# JurgenFolder.net
KiCad netlist of a schematic drawn in EAGLE
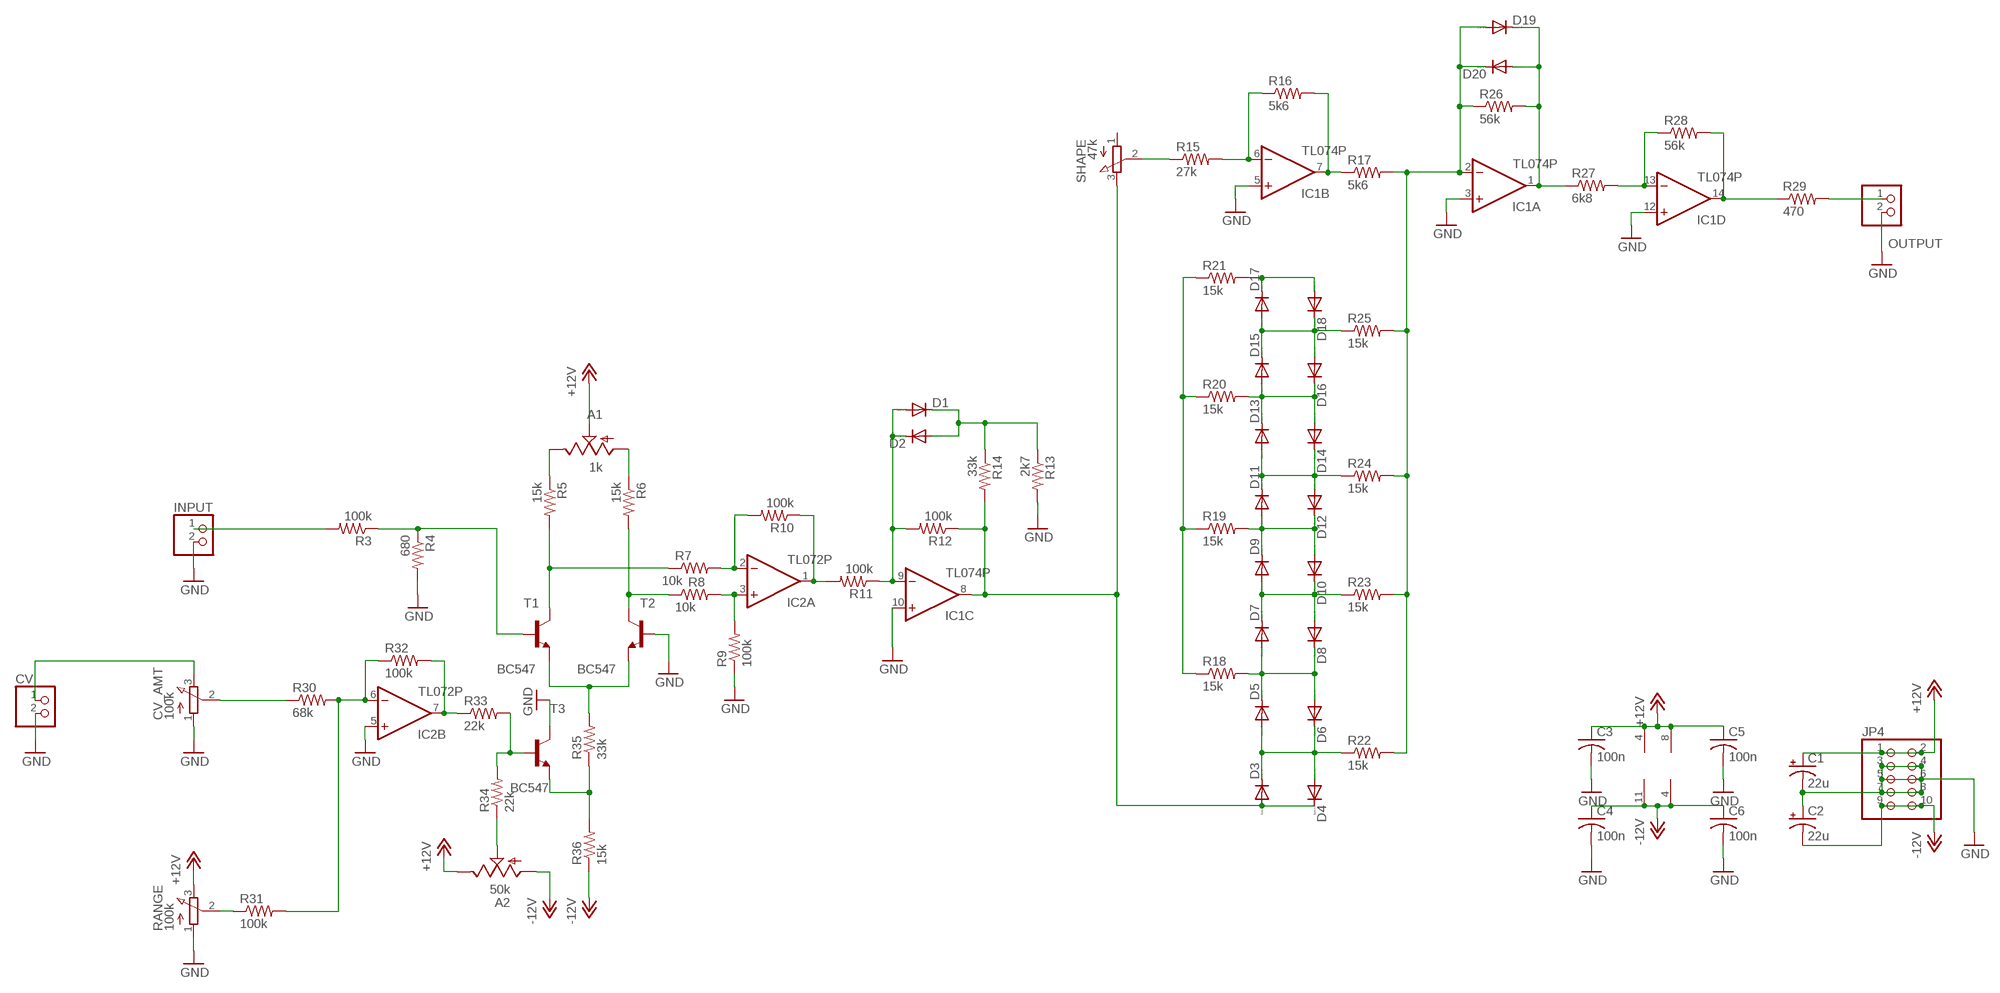
[diagram p0: schematic, sheet 1]

(export (version "E")
  (design (tool "Eeschema 10.0.6"))
  (components
    (comp (ref "A1")
      (value "1k")
      (footprint "eagle-import:S64W")
      (libsource (lib "eagle-import") (part "TRIM_US-S64W"))
    )
    (comp (ref "A2")
      (value "50k")
      (footprint "eagle-import:S64W")
      (libsource (lib "eagle-import") (part "TRIM_US-S64W"))
    )
    (comp (ref "C1")
      (value "22u")
      (footprint "eagle-import:E3,5-8")
      (libsource (lib "eagle-import") (part "CPOL-USE3.5-8"))
    )
    (comp (ref "C2")
      (value "22u")
      (footprint "eagle-import:E3,5-8")
      (libsource (lib "eagle-import") (part "CPOL-USE3.5-8"))
    )
    (comp (ref "C3")
      (value "100n")
      (footprint "eagle-import:C025-030X050")
      (libsource (lib "eagle-import") (part "C-US025-030X050"))
    )
    (comp (ref "C4")
      (value "100n")
      (footprint "eagle-import:C025-030X050")
      (libsource (lib "eagle-import") (part "C-US025-030X050"))
    )
    (comp (ref "C5")
      (value "100n")
      (footprint "eagle-import:C025-030X050")
      (libsource (lib "eagle-import") (part "C-US025-030X050"))
    )
    (comp (ref "C6")
      (value "100n")
      (footprint "eagle-import:C025-030X050")
      (libsource (lib "eagle-import") (part "C-US025-030X050"))
    )
    (comp (ref "CV")
      (value "PINHD-1X2")
      (footprint "eagle-import:1X02")
      (libsource (lib "eagle-import") (part "PINHD-1X2"))
    )
    (comp (ref "CV_AMT")
      (value "100k")
      (footprint "eagle-import:3RP_1610N")
      (libsource (lib "eagle-import") (part "3RP/1610N"))
    )
    (comp (ref "D1")
      (value "1N4148DO35-7")
      (footprint "eagle-import:DO35-7")
      (libsource (lib "eagle-import") (part "1N4148DO35-7"))
    )
    (comp (ref "D2")
      (value "1N4148DO35-7")
      (footprint "eagle-import:DO35-7")
      (libsource (lib "eagle-import") (part "1N4148DO35-7"))
    )
    (comp (ref "D3")
      (value "1N4148DO35-7")
      (footprint "eagle-import:DO35-7")
      (libsource (lib "eagle-import") (part "1N4148DO35-7"))
    )
    (comp (ref "D4")
      (value "1N4148DO35-7")
      (footprint "eagle-import:DO35-7")
      (libsource (lib "eagle-import") (part "1N4148DO35-7"))
    )
    (comp (ref "D5")
      (value "1N4148DO35-7")
      (footprint "eagle-import:DO35-7")
      (libsource (lib "eagle-import") (part "1N4148DO35-7"))
    )
    (comp (ref "D6")
      (value "1N4148DO35-7")
      (footprint "eagle-import:DO35-7")
      (libsource (lib "eagle-import") (part "1N4148DO35-7"))
    )
    (comp (ref "D7")
      (value "1N4148DO35-7")
      (footprint "eagle-import:DO35-7")
      (libsource (lib "eagle-import") (part "1N4148DO35-7"))
    )
    (comp (ref "D8")
      (value "1N4148DO35-7")
      (footprint "eagle-import:DO35-7")
      (libsource (lib "eagle-import") (part "1N4148DO35-7"))
    )
    (comp (ref "D9")
      (value "1N4148DO35-7")
      (footprint "eagle-import:DO35-7")
      (libsource (lib "eagle-import") (part "1N4148DO35-7"))
    )
    (comp (ref "D10")
      (value "1N4148DO35-7")
      (footprint "eagle-import:DO35-7")
      (libsource (lib "eagle-import") (part "1N4148DO35-7"))
    )
    (comp (ref "D11")
      (value "1N4148DO35-7")
      (footprint "eagle-import:DO35-7")
      (libsource (lib "eagle-import") (part "1N4148DO35-7"))
    )
    (comp (ref "D12")
      (value "1N4148DO35-7")
      (footprint "eagle-import:DO35-7")
      (libsource (lib "eagle-import") (part "1N4148DO35-7"))
    )
    (comp (ref "D13")
      (value "1N4148DO35-7")
      (footprint "eagle-import:DO35-7")
      (libsource (lib "eagle-import") (part "1N4148DO35-7"))
    )
    (comp (ref "D14")
      (value "1N4148DO35-7")
      (footprint "eagle-import:DO35-7")
      (libsource (lib "eagle-import") (part "1N4148DO35-7"))
    )
    (comp (ref "D15")
      (value "1N4148DO35-7")
      (footprint "eagle-import:DO35-7")
      (libsource (lib "eagle-import") (part "1N4148DO35-7"))
    )
    (comp (ref "D16")
      (value "1N4148DO35-7")
      (footprint "eagle-import:DO35-7")
      (libsource (lib "eagle-import") (part "1N4148DO35-7"))
    )
    (comp (ref "D17")
      (value "1N4148DO35-7")
      (footprint "eagle-import:DO35-7")
      (libsource (lib "eagle-import") (part "1N4148DO35-7"))
    )
    (comp (ref "D18")
      (value "1N4148DO35-7")
      (footprint "eagle-import:DO35-7")
      (libsource (lib "eagle-import") (part "1N4148DO35-7"))
    )
    (comp (ref "D19")
      (value "1N4148DO35-7")
      (footprint "eagle-import:DO35-7")
      (libsource (lib "eagle-import") (part "1N4148DO35-7"))
    )
    (comp (ref "D20")
      (value "1N4148DO35-7")
      (footprint "eagle-import:DO35-7")
      (libsource (lib "eagle-import") (part "1N4148DO35-7"))
    )
    (comp (ref "IC1")
      (value "TL074P")
      (footprint "eagle-import:DIL14")
      (libsource (lib "eagle-import") (part "TL074P"))
    )
    (comp (ref "IC2")
      (value "TL072P")
      (footprint "eagle-import:DIL08")
      (libsource (lib "eagle-import") (part "TL072P"))
    )
    (comp (ref "INPUT")
      (value "PINHD-1X2")
      (footprint "eagle-import:1X02")
      (libsource (lib "eagle-import") (part "PINHD-1X2"))
    )
    (comp (ref "JP4")
      (value "PINHD-2X5")
      (footprint "eagle-import:2X05")
      (libsource (lib "eagle-import") (part "PINHD-2X5"))
    )
    (comp (ref "OUTPUT")
      (value "PINHD-1X2")
      (footprint "eagle-import:1X02")
      (libsource (lib "eagle-import") (part "PINHD-1X2"))
    )
    (comp (ref "R3")
      (value "100k")
      (footprint "eagle-import:0204_7")
      (libsource (lib "eagle-import") (part "R-US_0204/7"))
    )
    (comp (ref "R4")
      (value "680")
      (footprint "eagle-import:0204_7")
      (libsource (lib "eagle-import") (part "R-US_0204/7"))
    )
    (comp (ref "R5")
      (value "15k")
      (footprint "eagle-import:0204_7")
      (libsource (lib "eagle-import") (part "R-US_0204/7"))
    )
    (comp (ref "R6")
      (value "15k")
      (footprint "eagle-import:0204_7")
      (libsource (lib "eagle-import") (part "R-US_0204/7"))
    )
    (comp (ref "R7")
      (value "10k")
      (footprint "eagle-import:0204_7")
      (libsource (lib "eagle-import") (part "R-US_0204/7"))
    )
    (comp (ref "R8")
      (value "10k")
      (footprint "eagle-import:0204_7")
      (libsource (lib "eagle-import") (part "R-US_0204/7"))
    )
    (comp (ref "R9")
      (value "100k")
      (footprint "eagle-import:0204_7")
      (libsource (lib "eagle-import") (part "R-US_0204/7"))
    )
    (comp (ref "R10")
      (value "100k")
      (footprint "eagle-import:0204_7")
      (libsource (lib "eagle-import") (part "R-US_0204/7"))
    )
    (comp (ref "R11")
      (value "100k")
      (footprint "eagle-import:0204_7")
      (libsource (lib "eagle-import") (part "R-US_0204/7"))
    )
    (comp (ref "R12")
      (value "100k")
      (footprint "eagle-import:0204_7")
      (libsource (lib "eagle-import") (part "R-US_0204/7"))
    )
    (comp (ref "R13")
      (value "2k7")
      (footprint "eagle-import:0204_7")
      (libsource (lib "eagle-import") (part "R-US_0204/7"))
    )
    (comp (ref "R14")
      (value "33k")
      (footprint "eagle-import:0204_7")
      (libsource (lib "eagle-import") (part "R-US_0204/7"))
    )
    (comp (ref "R15")
      (value "27k")
      (footprint "eagle-import:0204_7")
      (libsource (lib "eagle-import") (part "R-US_0204/7"))
    )
    (comp (ref "R16")
      (value "5k6")
      (footprint "eagle-import:0204_7")
      (libsource (lib "eagle-import") (part "R-US_0204/7"))
    )
    (comp (ref "R17")
      (value "5k6")
      (footprint "eagle-import:0204_7")
      (libsource (lib "eagle-import") (part "R-US_0204/7"))
    )
    (comp (ref "R18")
      (value "15k")
      (footprint "eagle-import:0204_7")
      (libsource (lib "eagle-import") (part "R-US_0204/7"))
    )
    (comp (ref "R19")
      (value "15k")
      (footprint "eagle-import:0204_7")
      (libsource (lib "eagle-import") (part "R-US_0204/7"))
    )
    (comp (ref "R20")
      (value "15k")
      (footprint "eagle-import:0204_7")
      (libsource (lib "eagle-import") (part "R-US_0204/7"))
    )
    (comp (ref "R21")
      (value "15k")
      (footprint "eagle-import:0204_7")
      (libsource (lib "eagle-import") (part "R-US_0204/7"))
    )
    (comp (ref "R22")
      (value "15k")
      (footprint "eagle-import:0204_7")
      (libsource (lib "eagle-import") (part "R-US_0204/7"))
    )
    (comp (ref "R23")
      (value "15k")
      (footprint "eagle-import:0204_7")
      (libsource (lib "eagle-import") (part "R-US_0204/7"))
    )
    (comp (ref "R24")
      (value "15k")
      (footprint "eagle-import:0204_7")
      (libsource (lib "eagle-import") (part "R-US_0204/7"))
    )
    (comp (ref "R25")
      (value "15k")
      (footprint "eagle-import:0204_7")
      (libsource (lib "eagle-import") (part "R-US_0204/7"))
    )
    (comp (ref "R26")
      (value "56k")
      (footprint "eagle-import:0204_7")
      (libsource (lib "eagle-import") (part "R-US_0204/7"))
    )
    (comp (ref "R27")
      (value "6k8")
      (footprint "eagle-import:0204_7")
      (libsource (lib "eagle-import") (part "R-US_0204/7"))
    )
    (comp (ref "R28")
      (value "56k")
      (footprint "eagle-import:0204_7")
      (libsource (lib "eagle-import") (part "R-US_0204/7"))
    )
    (comp (ref "R29")
      (value "470")
      (footprint "eagle-import:0204_7")
      (libsource (lib "eagle-import") (part "R-US_0204/7"))
    )
    (comp (ref "R30")
      (value "68k")
      (footprint "eagle-import:0204_7")
      (libsource (lib "eagle-import") (part "R-US_0204/7"))
    )
    (comp (ref "R31")
      (value "100k")
      (footprint "eagle-import:0204_7")
      (libsource (lib "eagle-import") (part "R-US_0204/7"))
    )
    (comp (ref "R32")
      (value "100k")
      (footprint "eagle-import:0204_7")
      (libsource (lib "eagle-import") (part "R-US_0204/7"))
    )
    (comp (ref "R33")
      (value "22k")
      (footprint "eagle-import:0204_7")
      (libsource (lib "eagle-import") (part "R-US_0204/7"))
    )
    (comp (ref "R34")
      (value "22k")
      (footprint "eagle-import:0204_7")
      (libsource (lib "eagle-import") (part "R-US_0204/7"))
    )
    (comp (ref "R35")
      (value "33k")
      (footprint "eagle-import:0204_7")
      (libsource (lib "eagle-import") (part "R-US_0204/7"))
    )
    (comp (ref "R36")
      (value "15k")
      (footprint "eagle-import:0204_7")
      (libsource (lib "eagle-import") (part "R-US_0204/7"))
    )
    (comp (ref "RANGE")
      (value "100k")
      (footprint "eagle-import:3RP_1610N")
      (libsource (lib "eagle-import") (part "3RP/1610N"))
    )
    (comp (ref "SHAPE")
      (value "47k")
      (footprint "eagle-import:3RP_1610N")
      (libsource (lib "eagle-import") (part "3RP/1610N"))
    )
    (comp (ref "T1")
      (value "BC547")
      (footprint "eagle-import:TO92")
      (libsource (lib "eagle-import") (part "BC547"))
    )
    (comp (ref "T2")
      (value "BC547")
      (footprint "eagle-import:TO92")
      (libsource (lib "eagle-import") (part "BC547"))
    )
    (comp (ref "T3")
      (value "BC547")
      (footprint "eagle-import:TO92")
      (libsource (lib "eagle-import") (part "BC547"))
    )
  )
  (nets
    (net (code "1") (name "+12V") (class "Default")
      (node (ref "A1") (pin "S") (pinfunction "S_S") (pintype "passive"))
      (node (ref "A2") (pin "E") (pinfunction "E_E") (pintype "passive"))
      (node (ref "C1") (pin "+") (pinfunction "+_+") (pintype "passive"))
      (node (ref "C3") (pin "1") (pinfunction "1_1") (pintype "passive"))
      (node (ref "C5") (pin "1") (pinfunction "1_1") (pintype "passive"))
      (node (ref "IC1") (pin "4") (pinfunction "V+_4") (pintype "power_in"))
      (node (ref "IC2") (pin "8") (pinfunction "V+_8") (pintype "power_in"))
      (node (ref "JP4") (pin "1") (pinfunction "1_1") (pintype "passive"))
      (node (ref "JP4") (pin "2") (pinfunction "2_2") (pintype "passive"))
      (node (ref "RANGE") (pin "3") (pinfunction "E_3") (pintype "passive"))
    )
    (net (code "2") (name "-12V") (class "Default")
      (node (ref "A2") (pin "A") (pinfunction "A_A") (pintype "passive"))
      (node (ref "C2") (pin "-") (pinfunction "-_-") (pintype "passive"))
      (node (ref "C4") (pin "1") (pinfunction "1_1") (pintype "passive"))
      (node (ref "C6") (pin "1") (pinfunction "1_1") (pintype "passive"))
      (node (ref "IC1") (pin "11") (pinfunction "V-_11") (pintype "power_in"))
      (node (ref "IC2") (pin "4") (pinfunction "V-_4") (pintype "power_in"))
      (node (ref "JP4") (pin "10") (pinfunction "10_10") (pintype "passive"))
      (node (ref "JP4") (pin "9") (pinfunction "9_9") (pintype "passive"))
      (node (ref "R36") (pin "1") (pinfunction "1_1") (pintype "passive"))
    )
    (net (code "3") (name "GND") (class "Default")
      (node (ref "C1") (pin "-") (pinfunction "-_-") (pintype "passive"))
      (node (ref "C2") (pin "+") (pinfunction "+_+") (pintype "passive"))
      (node (ref "C3") (pin "2") (pinfunction "2_2") (pintype "passive"))
      (node (ref "C4") (pin "2") (pinfunction "2_2") (pintype "passive"))
      (node (ref "C5") (pin "2") (pinfunction "2_2") (pintype "passive"))
      (node (ref "C6") (pin "2") (pinfunction "2_2") (pintype "passive"))
      (node (ref "CV") (pin "2") (pinfunction "2_2") (pintype "passive"))
      (node (ref "CV_AMT") (pin "1") (pinfunction "A_1") (pintype "passive"))
      (node (ref "IC1") (pin "10") (pinfunction "+IN_10") (pintype "input"))
      (node (ref "IC1") (pin "12") (pinfunction "+IN_12") (pintype "input"))
      (node (ref "IC1") (pin "3") (pinfunction "+IN_3") (pintype "input"))
      (node (ref "IC1") (pin "5") (pinfunction "+IN_5") (pintype "input"))
      (node (ref "IC2") (pin "5") (pinfunction "+IN_5") (pintype "input"))
      (node (ref "INPUT") (pin "2") (pinfunction "2_2") (pintype "passive"))
      (node (ref "JP4") (pin "3") (pinfunction "3_3") (pintype "passive"))
      (node (ref "JP4") (pin "4") (pinfunction "4_4") (pintype "passive"))
      (node (ref "JP4") (pin "5") (pinfunction "5_5") (pintype "passive"))
      (node (ref "JP4") (pin "6") (pinfunction "6_6") (pintype "passive"))
      (node (ref "JP4") (pin "7") (pinfunction "7_7") (pintype "passive"))
      (node (ref "JP4") (pin "8") (pinfunction "8_8") (pintype "passive"))
      (node (ref "OUTPUT") (pin "2") (pinfunction "2_2") (pintype "passive"))
      (node (ref "R13") (pin "2") (pinfunction "2_2") (pintype "passive"))
      (node (ref "R4") (pin "2") (pinfunction "2_2") (pintype "passive"))
      (node (ref "R9") (pin "1") (pinfunction "1_1") (pintype "passive"))
      (node (ref "RANGE") (pin "1") (pinfunction "A_1") (pintype "passive"))
      (node (ref "T2") (pin "2") (pinfunction "B_2") (pintype "passive"))
      (node (ref "T3") (pin "3") (pinfunction "C_3") (pintype "passive"))
    )
    (net (code "4") (name "Net-(A1-PadA)") (class "Default")
      (node (ref "A1") (pin "A") (pinfunction "A_A") (pintype "passive"))
      (node (ref "R6") (pin "1") (pinfunction "1_1") (pintype "passive"))
    )
    (net (code "5") (name "Net-(A1-PadE)") (class "Default")
      (node (ref "A1") (pin "E") (pinfunction "E_E") (pintype "passive"))
      (node (ref "R5") (pin "1") (pinfunction "1_1") (pintype "passive"))
    )
    (net (code "6") (name "Net-(A2-PadS)") (class "Default")
      (node (ref "A2") (pin "S") (pinfunction "S_S") (pintype "passive"))
      (node (ref "R34") (pin "1") (pinfunction "1_1") (pintype "passive"))
    )
    (net (code "7") (name "Net-(CV_AMT-E)") (class "Default")
      (node (ref "CV") (pin "1") (pinfunction "1_1") (pintype "passive"))
      (node (ref "CV_AMT") (pin "3") (pinfunction "E_3") (pintype "passive"))
    )
    (net (code "8") (name "Net-(CV_AMT-S)") (class "Default")
      (node (ref "CV_AMT") (pin "2") (pinfunction "S_2") (pintype "passive"))
      (node (ref "R30") (pin "1") (pinfunction "1_1") (pintype "passive"))
    )
    (net (code "9") (name "Net-(D1-PadC)") (class "Default")
      (node (ref "D1") (pin "C") (pinfunction "C_C") (pintype "passive"))
      (node (ref "D2") (pin "A") (pinfunction "A_A") (pintype "passive"))
      (node (ref "R13") (pin "1") (pinfunction "1_1") (pintype "passive"))
      (node (ref "R14") (pin "1") (pinfunction "1_1") (pintype "passive"))
    )
    (net (code "10") (name "Net-(D3-PadC)") (class "Default")
      (node (ref "D3") (pin "C") (pinfunction "C_C") (pintype "passive"))
      (node (ref "D4") (pin "A") (pinfunction "A_A") (pintype "passive"))
      (node (ref "D5") (pin "A") (pinfunction "A_A") (pintype "passive"))
      (node (ref "D6") (pin "C") (pinfunction "C_C") (pintype "passive"))
      (node (ref "R22") (pin "1") (pinfunction "1_1") (pintype "passive"))
    )
    (net (code "11") (name "Net-(D5-PadC)") (class "Default")
      (node (ref "D5") (pin "C") (pinfunction "C_C") (pintype "passive"))
      (node (ref "D6") (pin "A") (pinfunction "A_A") (pintype "passive"))
      (node (ref "D7") (pin "A") (pinfunction "A_A") (pintype "passive"))
      (node (ref "D8") (pin "C") (pinfunction "C_C") (pintype "passive"))
      (node (ref "R18") (pin "2") (pinfunction "2_2") (pintype "passive"))
    )
    (net (code "12") (name "Net-(D10-PadA)") (class "Default")
      (node (ref "D10") (pin "A") (pinfunction "A_A") (pintype "passive"))
      (node (ref "D11") (pin "A") (pinfunction "A_A") (pintype "passive"))
      (node (ref "D12") (pin "C") (pinfunction "C_C") (pintype "passive"))
      (node (ref "D9") (pin "C") (pinfunction "C_C") (pintype "passive"))
      (node (ref "R19") (pin "2") (pinfunction "2_2") (pintype "passive"))
    )
    (net (code "13") (name "Net-(D10-PadC)") (class "Default")
      (node (ref "D10") (pin "C") (pinfunction "C_C") (pintype "passive"))
      (node (ref "D7") (pin "C") (pinfunction "C_C") (pintype "passive"))
      (node (ref "D8") (pin "A") (pinfunction "A_A") (pintype "passive"))
      (node (ref "D9") (pin "A") (pinfunction "A_A") (pintype "passive"))
      (node (ref "R23") (pin "1") (pinfunction "1_1") (pintype "passive"))
    )
    (net (code "14") (name "Net-(D11-PadC)") (class "Default")
      (node (ref "D11") (pin "C") (pinfunction "C_C") (pintype "passive"))
      (node (ref "D12") (pin "A") (pinfunction "A_A") (pintype "passive"))
      (node (ref "D13") (pin "A") (pinfunction "A_A") (pintype "passive"))
      (node (ref "D14") (pin "C") (pinfunction "C_C") (pintype "passive"))
      (node (ref "R24") (pin "1") (pinfunction "1_1") (pintype "passive"))
    )
    (net (code "15") (name "Net-(D13-PadC)") (class "Default")
      (node (ref "D13") (pin "C") (pinfunction "C_C") (pintype "passive"))
      (node (ref "D14") (pin "A") (pinfunction "A_A") (pintype "passive"))
      (node (ref "D15") (pin "A") (pinfunction "A_A") (pintype "passive"))
      (node (ref "D16") (pin "C") (pinfunction "C_C") (pintype "passive"))
      (node (ref "R20") (pin "2") (pinfunction "2_2") (pintype "passive"))
    )
    (net (code "16") (name "Net-(D15-PadC)") (class "Default")
      (node (ref "D15") (pin "C") (pinfunction "C_C") (pintype "passive"))
      (node (ref "D16") (pin "A") (pinfunction "A_A") (pintype "passive"))
      (node (ref "D17") (pin "A") (pinfunction "A_A") (pintype "passive"))
      (node (ref "D18") (pin "C") (pinfunction "C_C") (pintype "passive"))
      (node (ref "R25") (pin "1") (pinfunction "1_1") (pintype "passive"))
    )
    (net (code "17") (name "Net-(D17-PadC)") (class "Default")
      (node (ref "D17") (pin "C") (pinfunction "C_C") (pintype "passive"))
      (node (ref "D18") (pin "A") (pinfunction "A_A") (pintype "passive"))
      (node (ref "R21") (pin "2") (pinfunction "2_2") (pintype "passive"))
    )
    (net (code "18") (name "Net-(IC1A--IN)") (class "Default")
      (node (ref "D19") (pin "A") (pinfunction "A_A") (pintype "passive"))
      (node (ref "D20") (pin "C") (pinfunction "C_C") (pintype "passive"))
      (node (ref "IC1") (pin "2") (pinfunction "-IN_2") (pintype "input"))
      (node (ref "R17") (pin "2") (pinfunction "2_2") (pintype "passive"))
      (node (ref "R22") (pin "2") (pinfunction "2_2") (pintype "passive"))
      (node (ref "R23") (pin "2") (pinfunction "2_2") (pintype "passive"))
      (node (ref "R24") (pin "2") (pinfunction "2_2") (pintype "passive"))
      (node (ref "R25") (pin "2") (pinfunction "2_2") (pintype "passive"))
      (node (ref "R26") (pin "1") (pinfunction "1_1") (pintype "passive"))
    )
    (net (code "19") (name "Net-(IC1A-OUT)") (class "Default")
      (node (ref "D19") (pin "C") (pinfunction "C_C") (pintype "passive"))
      (node (ref "D20") (pin "A") (pinfunction "A_A") (pintype "passive"))
      (node (ref "IC1") (pin "1") (pinfunction "OUT_1") (pintype "output"))
      (node (ref "R26") (pin "2") (pinfunction "2_2") (pintype "passive"))
      (node (ref "R27") (pin "1") (pinfunction "1_1") (pintype "passive"))
    )
    (net (code "20") (name "Net-(IC1B--IN)") (class "Default")
      (node (ref "IC1") (pin "6") (pinfunction "-IN_6") (pintype "input"))
      (node (ref "R15") (pin "2") (pinfunction "2_2") (pintype "passive"))
      (node (ref "R16") (pin "1") (pinfunction "1_1") (pintype "passive"))
    )
    (net (code "21") (name "Net-(IC1B-OUT)") (class "Default")
      (node (ref "IC1") (pin "7") (pinfunction "OUT_7") (pintype "output"))
      (node (ref "R16") (pin "2") (pinfunction "2_2") (pintype "passive"))
      (node (ref "R17") (pin "1") (pinfunction "1_1") (pintype "passive"))
    )
    (net (code "22") (name "Net-(IC1C--IN)") (class "Default")
      (node (ref "D1") (pin "A") (pinfunction "A_A") (pintype "passive"))
      (node (ref "D2") (pin "C") (pinfunction "C_C") (pintype "passive"))
      (node (ref "IC1") (pin "9") (pinfunction "-IN_9") (pintype "input"))
      (node (ref "R11") (pin "1") (pinfunction "1_1") (pintype "passive"))
      (node (ref "R12") (pin "2") (pinfunction "2_2") (pintype "passive"))
    )
    (net (code "23") (name "Net-(IC1C-OUT)") (class "Default")
      (node (ref "D3") (pin "A") (pinfunction "A_A") (pintype "passive"))
      (node (ref "D4") (pin "C") (pinfunction "C_C") (pintype "passive"))
      (node (ref "IC1") (pin "8") (pinfunction "OUT_8") (pintype "output"))
      (node (ref "R12") (pin "1") (pinfunction "1_1") (pintype "passive"))
      (node (ref "R14") (pin "2") (pinfunction "2_2") (pintype "passive"))
      (node (ref "SHAPE") (pin "3") (pinfunction "E_3") (pintype "passive"))
    )
    (net (code "24") (name "Net-(IC1D--IN)") (class "Default")
      (node (ref "IC1") (pin "13") (pinfunction "-IN_13") (pintype "input"))
      (node (ref "R27") (pin "2") (pinfunction "2_2") (pintype "passive"))
      (node (ref "R28") (pin "1") (pinfunction "1_1") (pintype "passive"))
    )
    (net (code "25") (name "Net-(IC1D-OUT)") (class "Default")
      (node (ref "IC1") (pin "14") (pinfunction "OUT_14") (pintype "output"))
      (node (ref "R28") (pin "2") (pinfunction "2_2") (pintype "passive"))
      (node (ref "R29") (pin "1") (pinfunction "1_1") (pintype "passive"))
    )
    (net (code "26") (name "Net-(IC2A-+IN)") (class "Default")
      (node (ref "IC2") (pin "3") (pinfunction "+IN_3") (pintype "input"))
      (node (ref "R8") (pin "2") (pinfunction "2_2") (pintype "passive"))
      (node (ref "R9") (pin "2") (pinfunction "2_2") (pintype "passive"))
    )
    (net (code "27") (name "Net-(IC2A--IN)") (class "Default")
      (node (ref "IC2") (pin "2") (pinfunction "-IN_2") (pintype "input"))
      (node (ref "R10") (pin "2") (pinfunction "2_2") (pintype "passive"))
      (node (ref "R7") (pin "2") (pinfunction "2_2") (pintype "passive"))
    )
    (net (code "28") (name "Net-(IC2A-OUT)") (class "Default")
      (node (ref "IC2") (pin "1") (pinfunction "OUT_1") (pintype "output"))
      (node (ref "R10") (pin "1") (pinfunction "1_1") (pintype "passive"))
      (node (ref "R11") (pin "2") (pinfunction "2_2") (pintype "passive"))
    )
    (net (code "29") (name "Net-(IC2B--IN)") (class "Default")
      (node (ref "IC2") (pin "6") (pinfunction "-IN_6") (pintype "input"))
      (node (ref "R30") (pin "2") (pinfunction "2_2") (pintype "passive"))
      (node (ref "R31") (pin "2") (pinfunction "2_2") (pintype "passive"))
      (node (ref "R32") (pin "1") (pinfunction "1_1") (pintype "passive"))
    )
    (net (code "30") (name "Net-(IC2B-OUT)") (class "Default")
      (node (ref "IC2") (pin "7") (pinfunction "OUT_7") (pintype "output"))
      (node (ref "R32") (pin "2") (pinfunction "2_2") (pintype "passive"))
      (node (ref "R33") (pin "1") (pinfunction "1_1") (pintype "passive"))
    )
    (net (code "31") (name "Net-(INPUT-Pad1)") (class "Default")
      (node (ref "INPUT") (pin "1") (pinfunction "1_1") (pintype "passive"))
      (node (ref "R3") (pin "2") (pinfunction "2_2") (pintype "passive"))
    )
    (net (code "32") (name "Net-(OUTPUT-Pad1)") (class "Default")
      (node (ref "OUTPUT") (pin "1") (pinfunction "1_1") (pintype "passive"))
      (node (ref "R29") (pin "2") (pinfunction "2_2") (pintype "passive"))
    )
    (net (code "33") (name "Net-(R18-Pad1)") (class "Default")
      (node (ref "R18") (pin "1") (pinfunction "1_1") (pintype "passive"))
      (node (ref "R19") (pin "1") (pinfunction "1_1") (pintype "passive"))
      (node (ref "R20") (pin "1") (pinfunction "1_1") (pintype "passive"))
      (node (ref "R21") (pin "1") (pinfunction "1_1") (pintype "passive"))
    )
    (net (code "34") (name "Net-(RANGE-S)") (class "Default")
      (node (ref "R31") (pin "1") (pinfunction "1_1") (pintype "passive"))
      (node (ref "RANGE") (pin "2") (pinfunction "S_2") (pintype "passive"))
    )
    (net (code "35") (name "Net-(SHAPE-S)") (class "Default")
      (node (ref "R15") (pin "1") (pinfunction "1_1") (pintype "passive"))
      (node (ref "SHAPE") (pin "2") (pinfunction "S_2") (pintype "passive"))
    )
    (net (code "36") (name "Net-(T1-B)") (class "Default")
      (node (ref "R3") (pin "1") (pinfunction "1_1") (pintype "passive"))
      (node (ref "R4") (pin "1") (pinfunction "1_1") (pintype "passive"))
      (node (ref "T1") (pin "2") (pinfunction "B_2") (pintype "passive"))
    )
    (net (code "37") (name "Net-(T1-C)") (class "Default")
      (node (ref "R5") (pin "2") (pinfunction "2_2") (pintype "passive"))
      (node (ref "R7") (pin "1") (pinfunction "1_1") (pintype "passive"))
      (node (ref "T1") (pin "3") (pinfunction "C_3") (pintype "passive"))
    )
    (net (code "38") (name "Net-(T1-E)") (class "Default")
      (node (ref "R35") (pin "2") (pinfunction "2_2") (pintype "passive"))
      (node (ref "T1") (pin "1") (pinfunction "E_1") (pintype "passive"))
      (node (ref "T2") (pin "1") (pinfunction "E_1") (pintype "passive"))
    )
    (net (code "39") (name "Net-(T2-C)") (class "Default")
      (node (ref "R6") (pin "2") (pinfunction "2_2") (pintype "passive"))
      (node (ref "R8") (pin "1") (pinfunction "1_1") (pintype "passive"))
      (node (ref "T2") (pin "3") (pinfunction "C_3") (pintype "passive"))
    )
    (net (code "40") (name "Net-(T3-B)") (class "Default")
      (node (ref "R33") (pin "2") (pinfunction "2_2") (pintype "passive"))
      (node (ref "R34") (pin "2") (pinfunction "2_2") (pintype "passive"))
      (node (ref "T3") (pin "2") (pinfunction "B_2") (pintype "passive"))
    )
    (net (code "41") (name "Net-(T3-E)") (class "Default")
      (node (ref "R35") (pin "1") (pinfunction "1_1") (pintype "passive"))
      (node (ref "R36") (pin "2") (pinfunction "2_2") (pintype "passive"))
      (node (ref "T3") (pin "1") (pinfunction "E_1") (pintype "passive"))
    )
    (net (code "42") (name "unconnected-(SHAPE-A-Pad1)") (class "Default")
      (node (ref "SHAPE") (pin "1") (pinfunction "A_1") (pintype "passive"))
    )
  )
)
